# analog-to-digital-stage.net
KiCad netlist of a schematic drawn in Altium Designer
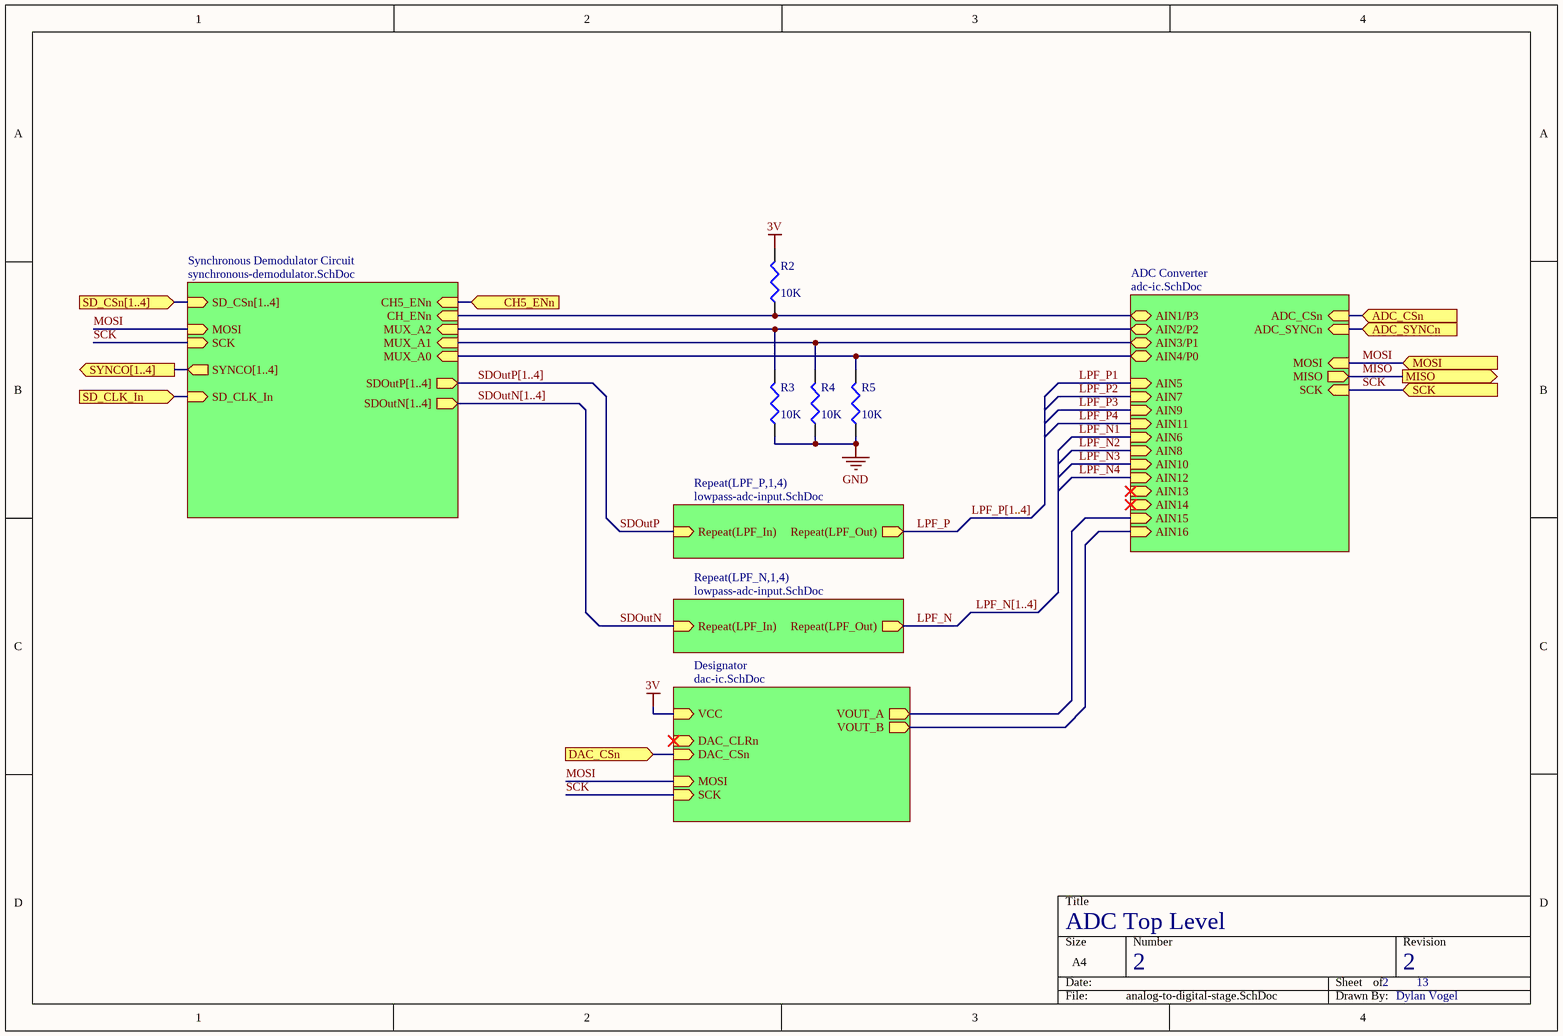
[diagram p0: analog-to-digital-stage.SchDoc]

(export (version "E")
  (design (tool "Eeschema 10.0.6"))
  (components
    (comp (ref "R2")
      (value "10K")
      (footprint "J1-0603")
      (description "10K pull-up for MUX ENn pin")
      (fields (field (name "PUBLISHER") "Altium Limited"))
      (libsource (lib "Miscellaneous Devices") (part "Res3"))
    )
    (comp (ref "R3")
      (value "10K")
      (footprint "J1-0603")
      (description "10K pulldown on MUX channel selection")
      (fields (field (name "PUBLISHER") "Altium Limited"))
      (libsource (lib "Miscellaneous Devices") (part "Res3"))
    )
    (comp (ref "R4")
      (value "10K")
      (footprint "J1-0603")
      (description "10K pulldown on MUX channel selection")
      (fields (field (name "PUBLISHER") "Altium Limited"))
      (libsource (lib "Miscellaneous Devices") (part "Res3"))
    )
    (comp (ref "R5")
      (value "10K")
      (footprint "J1-0603")
      (description "10K pulldown on MUX channel selection")
      (fields (field (name "PUBLISHER") "Altium Limited"))
      (libsource (lib "Miscellaneous Devices") (part "Res3"))
    )
  )
  (nets
    (net (code "19") (name "/AIN1{slash}P3") (class "Default")
      (node (ref "R2") (pin "1") (pinfunction "1_1") (pintype "passive"))
    )
    (net (code "20") (name "/AIN2{slash}P2") (class "Default")
      (node (ref "R3") (pin "2") (pinfunction "2_2") (pintype "passive"))
    )
    (net (code "21") (name "/AIN3{slash}P1") (class "Default")
      (node (ref "R4") (pin "2") (pinfunction "2_2") (pintype "passive"))
    )
    (net (code "22") (name "/AIN4{slash}P0") (class "Default")
      (node (ref "R5") (pin "2") (pinfunction "2_2") (pintype "passive"))
    )
    (net (code "52") (name "3V") (class "Default")
      (node (ref "R2") (pin "2") (pinfunction "2_2") (pintype "passive"))
    )
    (net (code "53") (name "GND") (class "Default")
      (node (ref "R3") (pin "1") (pinfunction "1_1") (pintype "passive"))
      (node (ref "R4") (pin "1") (pinfunction "1_1") (pintype "passive"))
      (node (ref "R5") (pin "1") (pinfunction "1_1") (pintype "passive"))
    )
  )
)
